# 1_INTERFACES_EXTERNAS.net
KiCad netlist of a schematic drawn in Altium Designer
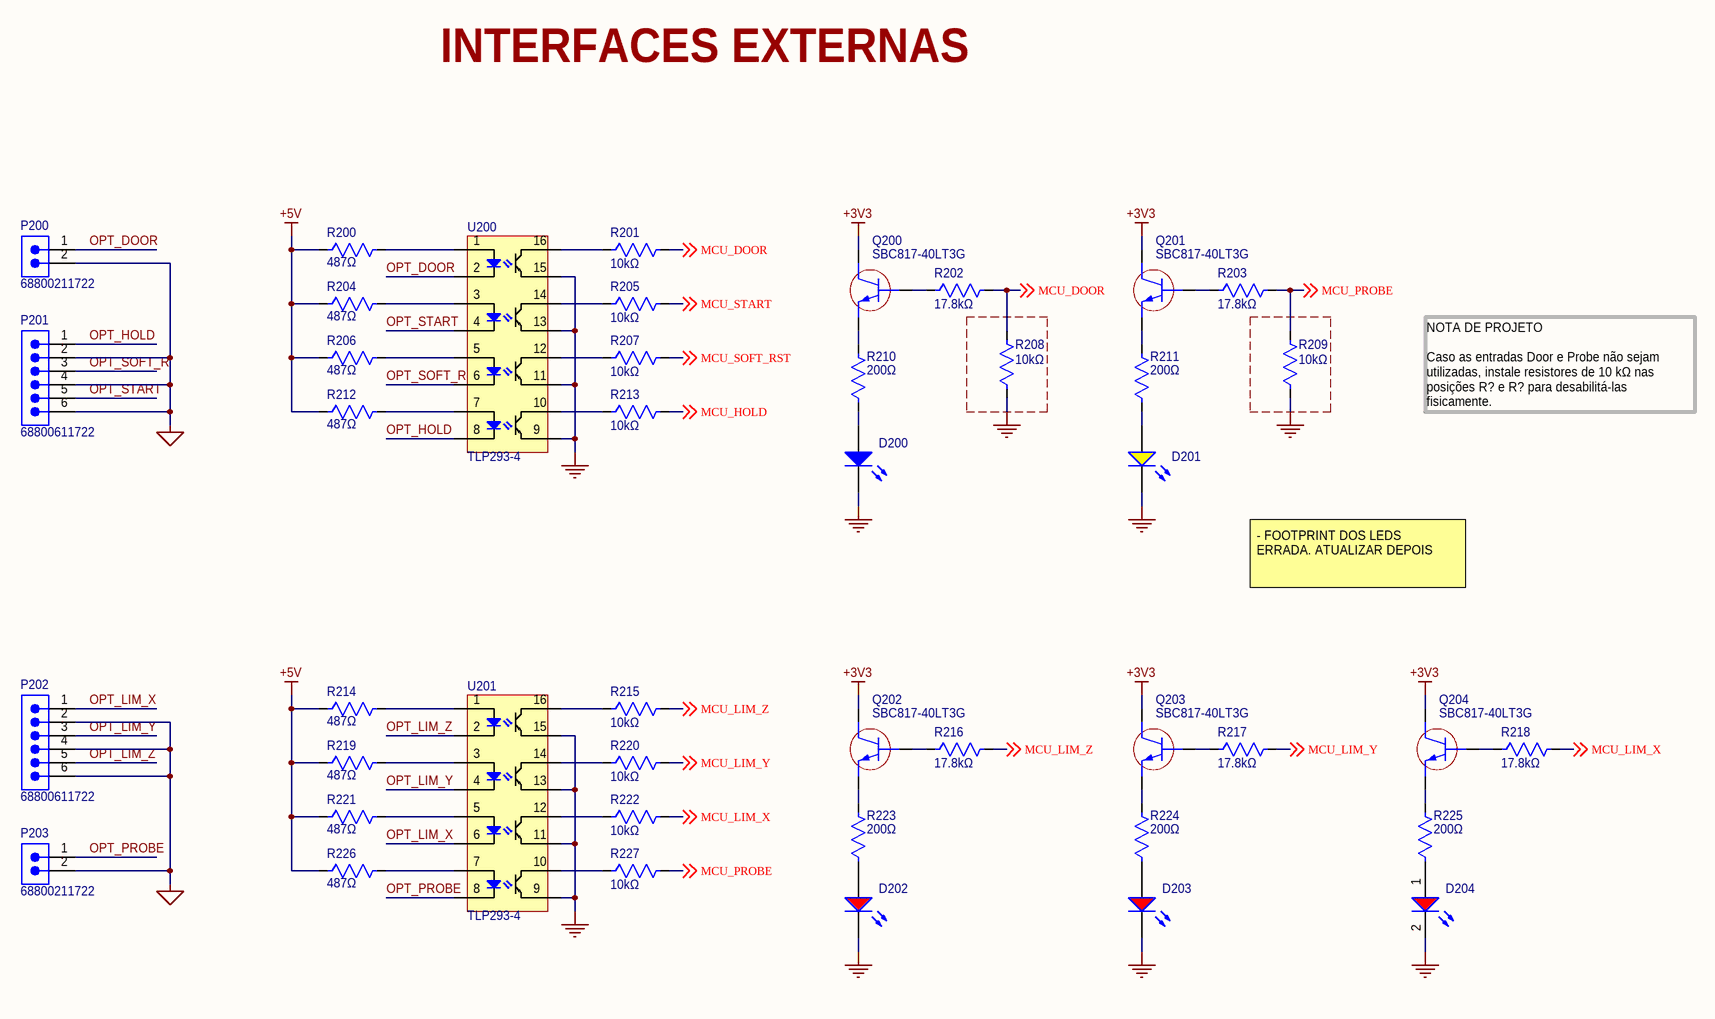
[diagram p0: 1_INTERFACES_EXTERNAS.SchDoc]

(export (version "E")
  (design (tool "Eeschema 10.0.6"))
  (components
    (comp (ref "D200")
      (value "Blue, 3.2V, 140deg")
      (footprint "WL-SMCW_0603_150060xx75003")
      (description "WL-SMCW Mono-color Chip LED Waterclear, SMT, size 0603, Blue, 3.2V, 140°")
      (fields
        (field (name "MANUFACTURER PART NUMBER") "150060BS75003")
        (field (name "MANUFACTURER") "Wurth Elektronik")
      )
      (libsource (lib "WE - Optoelectronic Components") (part "LED_Blue_1A-2K"))
    )
    (comp (ref "D201")
      (value "Yellow, 2V, 140deg")
      (footprint "WL-SMCW_0603_150060xx75000")
      (description "WL-SMCW Mono-color Chip LED Waterclear, SMT, size 0603, Yellow, 2V, 140°")
      (fields
        (field (name "MANUFACTURER PART NUMBER") "150060YS75000")
        (field (name "MANUFACTURER") "Wurth Elektronik")
      )
      (libsource (lib "WE - Optoelectronic Components") (part "LED_Yellow_2A-1K"))
    )
    (comp (ref "D202")
      (value "Red, 2V, 140deg")
      (footprint "WL-SMCW_0603_150060xx75003")
      (description "WL-SMCW Mono-color Chip LED Waterclear, SMT, size 0603, Red, 2V, 140°")
      (fields
        (field (name "MANUFACTURER PART NUMBER") "150060RS75003")
        (field (name "MANUFACTURER") "Wurth Elektronik")
      )
      (libsource (lib "") (part "LED_Red_1A-2K_1"))
    )
    (comp (ref "D203")
      (value "Red, 2V, 140deg")
      (footprint "WL-SMCW_0603_150060xx75003")
      (description "WL-SMCW Mono-color Chip LED Waterclear, SMT, size 0603, Red, 2V, 140°")
      (fields
        (field (name "MANUFACTURER PART NUMBER") "150060RS75003")
        (field (name "MANUFACTURER") "Wurth Elektronik")
      )
      (libsource (lib "") (part "LED_Red_1A-2K_1"))
    )
    (comp (ref "D204")
      (value "Red, 2V, 140deg")
      (footprint "WL-SMCW_0603_150060xx75003")
      (description "WL-SMCW Mono-color Chip LED Waterclear, SMT, size 0603, Red, 2V, 140°")
      (fields
        (field (name "MANUFACTURER PART NUMBER") "150060RS75003")
        (field (name "MANUFACTURER") "Wurth Elektronik")
      )
      (libsource (lib "WE - Optoelectronic Components") (part "LED_Red_1A-2K"))
    )
    (comp (ref "P200")
      (value "68800211722")
      (footprint "68800211722")
      (description "WR-WTB “J” Type THT Male Horizontal Shrouded Header, pitch 2.5 mm, 2 pins")
      (fields (field (name "MANUFACTURER") "Wurth Elektronik"))
      (libsource (lib "WE - Electromechanical Components") (part "Header_Male_1R_02P"))
    )
    (comp (ref "P201")
      (value "68800611722")
      (footprint "68800611722")
      (description "WR-WTB “J” Type THT Male Horizontal Shrouded Header, pitch 2.5 mm, 6 pins")
      (fields (field (name "MANUFACTURER") "Wurth Elektronik"))
      (libsource (lib "WE - Electromechanical Components") (part "Header_Male_1R_06P"))
    )
    (comp (ref "P202")
      (value "68800611722")
      (footprint "68800611722")
      (description "WR-WTB “J” Type THT Male Horizontal Shrouded Header, pitch 2.5 mm, 6 pins")
      (fields (field (name "MANUFACTURER") "Wurth Elektronik"))
      (libsource (lib "WE - Electromechanical Components") (part "Header_Male_1R_06P"))
    )
    (comp (ref "P203")
      (value "68800211722")
      (footprint "68800211722")
      (description "WR-WTB “J” Type THT Male Horizontal Shrouded Header, pitch 2.5 mm, 2 pins")
      (fields (field (name "MANUFACTURER") "Wurth Elektronik"))
      (libsource (lib "WE - Electromechanical Components") (part "Header_Male_1R_02P"))
    )
    (comp (ref "Q200")
      (value "SBC817-40LT3G")
      (footprint "SOT-23-3")
      (description "TRANS NPN 45V 0.5A SOT23-3")
      (fields (field (name "MANUFACTURER") "onsemi"))
      (libsource (lib "Transistors") (part "SBC817-40LT3G"))
    )
    (comp (ref "Q201")
      (value "SBC817-40LT3G")
      (footprint "SOT-23-3")
      (description "TRANS NPN 45V 0.5A SOT23-3")
      (fields (field (name "MANUFACTURER") "onsemi"))
      (libsource (lib "Transistors") (part "SBC817-40LT3G"))
    )
    (comp (ref "Q202")
      (value "SBC817-40LT3G")
      (footprint "SOT-23-3")
      (description "TRANS NPN 45V 0.5A SOT23-3")
      (fields (field (name "MANUFACTURER") "onsemi"))
      (libsource (lib "Transistors") (part "SBC817-40LT3G"))
    )
    (comp (ref "Q203")
      (value "SBC817-40LT3G")
      (footprint "SOT-23-3")
      (description "TRANS NPN 45V 0.5A SOT23-3")
      (fields (field (name "MANUFACTURER") "onsemi"))
      (libsource (lib "Transistors") (part "SBC817-40LT3G"))
    )
    (comp (ref "Q204")
      (value "SBC817-40LT3G")
      (footprint "SOT-23-3")
      (description "TRANS NPN 45V 0.5A SOT23-3")
      (fields (field (name "MANUFACTURER") "onsemi"))
      (libsource (lib "Transistors") (part "SBC817-40LT3G"))
    )
    (comp (ref "R200")
      (value "487Ω")
      (footprint "0603-WAVE")
      (description "RES 487 OHM 1% 1/10W 0603")
      (fields
        (field (name "MANUFACTURER PART NUMBER") "RC0603FR-07487RL")
        (field (name "MANUFACTURER") "Yageo Group")
      )
      (libsource (lib "Resistors-0603-E96-Yageo") (part "RC0603FR-07487RL"))
    )
    (comp (ref "R201")
      (value "10kΩ")
      (footprint "0603-WAVE")
      (description "RES 10K OHM 1% 1/10W 0603")
      (fields
        (field (name "MANUFACTURER PART NUMBER") "RC0603FR-0710KL")
        (field (name "MANUFACTURER") "Yageo Group")
      )
      (libsource (lib "Resistors-0603-E96-Yageo") (part "RC0603FR-0710KL"))
    )
    (comp (ref "R202")
      (value "17.8kΩ")
      (footprint "0603-WAVE")
      (description "RES 17.8K OHM 1% 1/10W 0603")
      (fields
        (field (name "MANUFACTURER PART NUMBER") "RC0603FR-0717K8L")
        (field (name "MANUFACTURER") "Yageo Group")
      )
      (libsource (lib "Resistors-0603-E96-Yageo") (part "RC0603FR-0717K8L"))
    )
    (comp (ref "R203")
      (value "17.8kΩ")
      (footprint "0603-WAVE")
      (description "RES 17.8K OHM 1% 1/10W 0603")
      (fields
        (field (name "MANUFACTURER PART NUMBER") "RC0603FR-0717K8L")
        (field (name "MANUFACTURER") "Yageo Group")
      )
      (libsource (lib "Resistors-0603-E96-Yageo") (part "RC0603FR-0717K8L"))
    )
    (comp (ref "R204")
      (value "487Ω")
      (footprint "0603-WAVE")
      (description "RES 487 OHM 1% 1/10W 0603")
      (fields
        (field (name "MANUFACTURER PART NUMBER") "RC0603FR-07487RL")
        (field (name "MANUFACTURER") "Yageo Group")
      )
      (libsource (lib "Resistors-0603-E96-Yageo") (part "RC0603FR-07487RL"))
    )
    (comp (ref "R205")
      (value "10kΩ")
      (footprint "0603-WAVE")
      (description "RES 10K OHM 1% 1/10W 0603")
      (fields
        (field (name "MANUFACTURER PART NUMBER") "RC0603FR-0710KL")
        (field (name "MANUFACTURER") "Yageo Group")
      )
      (libsource (lib "Resistors-0603-E96-Yageo") (part "RC0603FR-0710KL"))
    )
    (comp (ref "R206")
      (value "487Ω")
      (footprint "0603-WAVE")
      (description "RES 487 OHM 1% 1/10W 0603")
      (fields
        (field (name "MANUFACTURER PART NUMBER") "RC0603FR-07487RL")
        (field (name "MANUFACTURER") "Yageo Group")
      )
      (libsource (lib "Resistors-0603-E96-Yageo") (part "RC0603FR-07487RL"))
    )
    (comp (ref "R207")
      (value "10kΩ")
      (footprint "0603-WAVE")
      (description "RES 10K OHM 1% 1/10W 0603")
      (fields
        (field (name "MANUFACTURER PART NUMBER") "RC0603FR-0710KL")
        (field (name "MANUFACTURER") "Yageo Group")
      )
      (libsource (lib "Resistors-0603-E96-Yageo") (part "RC0603FR-0710KL"))
    )
    (comp (ref "R208")
      (value "10kΩ")
      (footprint "0603-WAVE")
      (description "RES 10K OHM 1% 1/10W 0603")
      (fields
        (field (name "MANUFACTURER PART NUMBER") "RC0603FR-0710KL")
        (field (name "MANUFACTURER") "Yageo Group")
      )
      (libsource (lib "Resistors-0603-E96-Yageo") (part "RC0603FR-0710KL"))
    )
    (comp (ref "R209")
      (value "10kΩ")
      (footprint "0603-WAVE")
      (description "RES 10K OHM 1% 1/10W 0603")
      (fields
        (field (name "MANUFACTURER PART NUMBER") "RC0603FR-0710KL")
        (field (name "MANUFACTURER") "Yageo Group")
      )
      (libsource (lib "Resistors-0603-E96-Yageo") (part "RC0603FR-0710KL"))
    )
    (comp (ref "R210")
      (value "200Ω")
      (footprint "0603-WAVE")
      (description "RES 200 OHM 1% 1/10W 0603")
      (fields
        (field (name "MANUFACTURER PART NUMBER") "RC0603FR-07200RL")
        (field (name "MANUFACTURER") "Yageo Group")
      )
      (libsource (lib "Resistors-0603-E96-Yageo") (part "RC0603FR-07200RL"))
    )
    (comp (ref "R211")
      (value "200Ω")
      (footprint "0603-WAVE")
      (description "RES 200 OHM 1% 1/10W 0603")
      (fields
        (field (name "MANUFACTURER PART NUMBER") "RC0603FR-07200RL")
        (field (name "MANUFACTURER") "Yageo Group")
      )
      (libsource (lib "Resistors-0603-E96-Yageo") (part "RC0603FR-07200RL"))
    )
    (comp (ref "R212")
      (value "487Ω")
      (footprint "0603-WAVE")
      (description "RES 487 OHM 1% 1/10W 0603")
      (fields
        (field (name "MANUFACTURER PART NUMBER") "RC0603FR-07487RL")
        (field (name "MANUFACTURER") "Yageo Group")
      )
      (libsource (lib "Resistors-0603-E96-Yageo") (part "RC0603FR-07487RL"))
    )
    (comp (ref "R213")
      (value "10kΩ")
      (footprint "0603-WAVE")
      (description "RES 10K OHM 1% 1/10W 0603")
      (fields
        (field (name "MANUFACTURER PART NUMBER") "RC0603FR-0710KL")
        (field (name "MANUFACTURER") "Yageo Group")
      )
      (libsource (lib "Resistors-0603-E96-Yageo") (part "RC0603FR-0710KL"))
    )
    (comp (ref "R214")
      (value "487Ω")
      (footprint "0603-WAVE")
      (description "RES 487 OHM 1% 1/10W 0603")
      (fields
        (field (name "MANUFACTURER PART NUMBER") "RC0603FR-07487RL")
        (field (name "MANUFACTURER") "Yageo Group")
      )
      (libsource (lib "Resistors-0603-E96-Yageo") (part "RC0603FR-07487RL"))
    )
    (comp (ref "R215")
      (value "10kΩ")
      (footprint "0603-WAVE")
      (description "RES 10K OHM 1% 1/10W 0603")
      (fields
        (field (name "MANUFACTURER PART NUMBER") "RC0603FR-0710KL")
        (field (name "MANUFACTURER") "Yageo Group")
      )
      (libsource (lib "Resistors-0603-E96-Yageo") (part "RC0603FR-0710KL"))
    )
    (comp (ref "R216")
      (value "17.8kΩ")
      (footprint "0603-WAVE")
      (description "RES 17.8K OHM 1% 1/10W 0603")
      (fields
        (field (name "MANUFACTURER PART NUMBER") "RC0603FR-0717K8L")
        (field (name "MANUFACTURER") "Yageo Group")
      )
      (libsource (lib "Resistors-0603-E96-Yageo") (part "RC0603FR-0717K8L"))
    )
    (comp (ref "R217")
      (value "17.8kΩ")
      (footprint "0603-WAVE")
      (description "RES 17.8K OHM 1% 1/10W 0603")
      (fields
        (field (name "MANUFACTURER PART NUMBER") "RC0603FR-0717K8L")
        (field (name "MANUFACTURER") "Yageo Group")
      )
      (libsource (lib "Resistors-0603-E96-Yageo") (part "RC0603FR-0717K8L"))
    )
    (comp (ref "R218")
      (value "17.8kΩ")
      (footprint "0603-WAVE")
      (description "RES 17.8K OHM 1% 1/10W 0603")
      (fields
        (field (name "MANUFACTURER PART NUMBER") "RC0603FR-0717K8L")
        (field (name "MANUFACTURER") "Yageo Group")
      )
      (libsource (lib "Resistors-0603-E96-Yageo") (part "RC0603FR-0717K8L"))
    )
    (comp (ref "R219")
      (value "487Ω")
      (footprint "0603-WAVE")
      (description "RES 487 OHM 1% 1/10W 0603")
      (fields
        (field (name "MANUFACTURER PART NUMBER") "RC0603FR-07487RL")
        (field (name "MANUFACTURER") "Yageo Group")
      )
      (libsource (lib "Resistors-0603-E96-Yageo") (part "RC0603FR-07487RL"))
    )
    (comp (ref "R220")
      (value "10kΩ")
      (footprint "0603-WAVE")
      (description "RES 10K OHM 1% 1/10W 0603")
      (fields
        (field (name "MANUFACTURER PART NUMBER") "RC0603FR-0710KL")
        (field (name "MANUFACTURER") "Yageo Group")
      )
      (libsource (lib "Resistors-0603-E96-Yageo") (part "RC0603FR-0710KL"))
    )
    (comp (ref "R221")
      (value "487Ω")
      (footprint "0603-WAVE")
      (description "RES 487 OHM 1% 1/10W 0603")
      (fields
        (field (name "MANUFACTURER PART NUMBER") "RC0603FR-07487RL")
        (field (name "MANUFACTURER") "Yageo Group")
      )
      (libsource (lib "Resistors-0603-E96-Yageo") (part "RC0603FR-07487RL"))
    )
    (comp (ref "R222")
      (value "10kΩ")
      (footprint "0603-WAVE")
      (description "RES 10K OHM 1% 1/10W 0603")
      (fields
        (field (name "MANUFACTURER PART NUMBER") "RC0603FR-0710KL")
        (field (name "MANUFACTURER") "Yageo Group")
      )
      (libsource (lib "Resistors-0603-E96-Yageo") (part "RC0603FR-0710KL"))
    )
    (comp (ref "R223")
      (value "200Ω")
      (footprint "0603-WAVE")
      (description "RES 200 OHM 1% 1/10W 0603")
      (fields
        (field (name "MANUFACTURER PART NUMBER") "RC0603FR-07200RL")
        (field (name "MANUFACTURER") "Yageo Group")
      )
      (libsource (lib "Resistors-0603-E96-Yageo") (part "RC0603FR-07200RL"))
    )
    (comp (ref "R224")
      (value "200Ω")
      (footprint "0603-WAVE")
      (description "RES 200 OHM 1% 1/10W 0603")
      (fields
        (field (name "MANUFACTURER PART NUMBER") "RC0603FR-07200RL")
        (field (name "MANUFACTURER") "Yageo Group")
      )
      (libsource (lib "Resistors-0603-E96-Yageo") (part "RC0603FR-07200RL"))
    )
    (comp (ref "R225")
      (value "200Ω")
      (footprint "0603-WAVE")
      (description "RES 200 OHM 1% 1/10W 0603")
      (fields
        (field (name "MANUFACTURER PART NUMBER") "RC0603FR-07200RL")
        (field (name "MANUFACTURER") "Yageo Group")
      )
      (libsource (lib "Resistors-0603-E96-Yageo") (part "RC0603FR-07200RL"))
    )
    (comp (ref "R226")
      (value "487Ω")
      (footprint "0603-WAVE")
      (description "RES 487 OHM 1% 1/10W 0603")
      (fields
        (field (name "MANUFACTURER PART NUMBER") "RC0603FR-07487RL")
        (field (name "MANUFACTURER") "Yageo Group")
      )
      (libsource (lib "Resistors-0603-E96-Yageo") (part "RC0603FR-07487RL"))
    )
    (comp (ref "R227")
      (value "10kΩ")
      (footprint "0603-WAVE")
      (description "RES 10K OHM 1% 1/10W 0603")
      (fields
        (field (name "MANUFACTURER PART NUMBER") "RC0603FR-0710KL")
        (field (name "MANUFACTURER") "Yageo Group")
      )
      (libsource (lib "Resistors-0603-E96-Yageo") (part "RC0603FR-0710KL"))
    )
    (comp (ref "U200")
      (value "TLP293-4")
      (footprint "SO-16")
      (description "OPTOISO 3.75KV 4CH TRANS 16-SO")
      (fields
        (field (name "MANUFACTURER") "Toshiba")
        (field (name "MANUFACTURER PART NUMBER") "TLP293-4(TP,E")
      )
      (libsource (lib "Optocouplers") (part "TLP293-4"))
    )
    (comp (ref "U201")
      (value "TLP293-4")
      (footprint "SO-16")
      (description "OPTOISO 3.75KV 4CH TRANS 16-SO")
      (fields
        (field (name "MANUFACTURER") "Toshiba")
        (field (name "MANUFACTURER PART NUMBER") "TLP293-4(TP,E")
      )
      (libsource (lib "Optocouplers") (part "TLP293-4"))
    )
  )
  (nets
    (net (code "1") (name "+3V3") (class "Default")
      (node (ref "Q200") (pin "3") (pinfunction "C_3") (pintype "passive"))
      (node (ref "Q201") (pin "3") (pinfunction "C_3") (pintype "passive"))
      (node (ref "Q202") (pin "3") (pinfunction "C_3") (pintype "passive"))
      (node (ref "Q203") (pin "3") (pinfunction "C_3") (pintype "passive"))
      (node (ref "Q204") (pin "3") (pinfunction "C_3") (pintype "passive"))
    )
    (net (code "2") (name "+5V") (class "Default")
      (node (ref "R200") (pin "1") (pinfunction "1_1") (pintype "passive"))
      (node (ref "R204") (pin "1") (pinfunction "1_1") (pintype "passive"))
      (node (ref "R206") (pin "1") (pinfunction "1_1") (pintype "passive"))
      (node (ref "R212") (pin "1") (pinfunction "1_1") (pintype "passive"))
      (node (ref "R214") (pin "1") (pinfunction "1_1") (pintype "passive"))
      (node (ref "R219") (pin "1") (pinfunction "1_1") (pintype "passive"))
      (node (ref "R221") (pin "1") (pinfunction "1_1") (pintype "passive"))
      (node (ref "R226") (pin "1") (pinfunction "1_1") (pintype "passive"))
    )
    (net (code "3") (name "/OPT_DOOR") (class "Default")
      (node (ref "P200") (pin "1") (pinfunction "1_1") (pintype "passive"))
      (node (ref "U200") (pin "2") (pinfunction "2_2") (pintype "passive"))
    )
    (net (code "4") (name "/OPT_HOLD") (class "Default")
      (node (ref "P201") (pin "1") (pinfunction "1_1") (pintype "passive"))
      (node (ref "U200") (pin "8") (pinfunction "8_8") (pintype "passive"))
    )
    (net (code "5") (name "/OPT_LIM_X") (class "Default")
      (node (ref "P202") (pin "1") (pinfunction "1_1") (pintype "passive"))
      (node (ref "U201") (pin "6") (pinfunction "6_6") (pintype "passive"))
    )
    (net (code "6") (name "/OPT_LIM_Y") (class "Default")
      (node (ref "P202") (pin "3") (pinfunction "3_3") (pintype "passive"))
      (node (ref "U201") (pin "4") (pinfunction "4_4") (pintype "passive"))
    )
    (net (code "7") (name "/OPT_LIM_Z") (class "Default")
      (node (ref "P202") (pin "5") (pinfunction "5_5") (pintype "passive"))
      (node (ref "U201") (pin "2") (pinfunction "2_2") (pintype "passive"))
    )
    (net (code "8") (name "/OPT_PROBE") (class "Default")
      (node (ref "P203") (pin "1") (pinfunction "1_1") (pintype "passive"))
      (node (ref "U201") (pin "8") (pinfunction "8_8") (pintype "passive"))
    )
    (net (code "9") (name "/OPT_SOFT_R") (class "Default")
      (node (ref "P201") (pin "3") (pinfunction "3_3") (pintype "passive"))
      (node (ref "U200") (pin "6") (pinfunction "6_6") (pintype "passive"))
    )
    (net (code "10") (name "/OPT_START") (class "Default")
      (node (ref "P201") (pin "5") (pinfunction "5_5") (pintype "passive"))
      (node (ref "U200") (pin "4") (pinfunction "4_4") (pintype "passive"))
    )
    (net (code "11") (name "GND") (class "Default")
      (node (ref "D200") (pin "2") (pinfunction "K_2") (pintype "passive"))
      (node (ref "D201") (pin "1") (pinfunction "K_1") (pintype "passive"))
      (node (ref "D202") (pin "2") (pinfunction "K_2") (pintype "passive"))
      (node (ref "D203") (pin "2") (pinfunction "K_2") (pintype "passive"))
      (node (ref "D204") (pin "2") (pinfunction "K_2") (pintype "passive"))
      (node (ref "R208") (pin "1") (pinfunction "1_1") (pintype "passive"))
      (node (ref "R209") (pin "1") (pinfunction "1_1") (pintype "passive"))
      (node (ref "U200") (pin "11") (pinfunction "11_11") (pintype "passive"))
      (node (ref "U200") (pin "13") (pinfunction "13_13") (pintype "passive"))
      (node (ref "U200") (pin "15") (pinfunction "15_15") (pintype "passive"))
      (node (ref "U200") (pin "9") (pinfunction "9_9") (pintype "passive"))
      (node (ref "U201") (pin "11") (pinfunction "11_11") (pintype "passive"))
      (node (ref "U201") (pin "13") (pinfunction "13_13") (pintype "passive"))
      (node (ref "U201") (pin "15") (pinfunction "15_15") (pintype "passive"))
      (node (ref "U201") (pin "9") (pinfunction "9_9") (pintype "passive"))
    )
    (net (code "12") (name "GND_ISO") (class "Default")
      (node (ref "P200") (pin "2") (pinfunction "2_2") (pintype "passive"))
      (node (ref "P201") (pin "2") (pinfunction "2_2") (pintype "passive"))
      (node (ref "P201") (pin "4") (pinfunction "4_4") (pintype "passive"))
      (node (ref "P201") (pin "6") (pinfunction "6_6") (pintype "passive"))
      (node (ref "P202") (pin "2") (pinfunction "2_2") (pintype "passive"))
      (node (ref "P202") (pin "4") (pinfunction "4_4") (pintype "passive"))
      (node (ref "P202") (pin "6") (pinfunction "6_6") (pintype "passive"))
      (node (ref "P203") (pin "2") (pinfunction "2_2") (pintype "passive"))
    )
    (net (code "13") (name "MCU_DOOR") (class "Default")
      (node (ref "R201") (pin "2") (pinfunction "2_2") (pintype "passive"))
      (node (ref "R202") (pin "2") (pinfunction "2_2") (pintype "passive"))
      (node (ref "R208") (pin "2") (pinfunction "2_2") (pintype "passive"))
    )
    (net (code "14") (name "MCU_HOLD") (class "Default")
      (node (ref "R213") (pin "2") (pinfunction "2_2") (pintype "passive"))
    )
    (net (code "15") (name "MCU_LIM_X") (class "Default")
      (node (ref "R218") (pin "2") (pinfunction "2_2") (pintype "passive"))
      (node (ref "R222") (pin "2") (pinfunction "2_2") (pintype "passive"))
    )
    (net (code "16") (name "MCU_LIM_Y") (class "Default")
      (node (ref "R217") (pin "2") (pinfunction "2_2") (pintype "passive"))
      (node (ref "R220") (pin "2") (pinfunction "2_2") (pintype "passive"))
    )
    (net (code "17") (name "MCU_LIM_Z") (class "Default")
      (node (ref "R215") (pin "2") (pinfunction "2_2") (pintype "passive"))
      (node (ref "R216") (pin "2") (pinfunction "2_2") (pintype "passive"))
    )
    (net (code "18") (name "MCU_PROBE") (class "Default")
      (node (ref "R203") (pin "2") (pinfunction "2_2") (pintype "passive"))
      (node (ref "R209") (pin "2") (pinfunction "2_2") (pintype "passive"))
      (node (ref "R227") (pin "2") (pinfunction "2_2") (pintype "passive"))
    )
    (net (code "19") (name "MCU_SOFT_RST") (class "Default")
      (node (ref "R207") (pin "2") (pinfunction "2_2") (pintype "passive"))
    )
    (net (code "20") (name "MCU_START") (class "Default")
      (node (ref "R205") (pin "2") (pinfunction "2_2") (pintype "passive"))
    )
    (net (code "21") (name "Net-(D200-A)") (class "Default")
      (node (ref "D200") (pin "1") (pinfunction "A_1") (pintype "passive"))
      (node (ref "R210") (pin "1") (pinfunction "1_1") (pintype "passive"))
    )
    (net (code "22") (name "Net-(D201-A)") (class "Default")
      (node (ref "D201") (pin "2") (pinfunction "A_2") (pintype "passive"))
      (node (ref "R211") (pin "1") (pinfunction "1_1") (pintype "passive"))
    )
    (net (code "23") (name "Net-(D202-A)") (class "Default")
      (node (ref "D202") (pin "1") (pinfunction "A_1") (pintype "passive"))
      (node (ref "R223") (pin "1") (pinfunction "1_1") (pintype "passive"))
    )
    (net (code "24") (name "Net-(D203-A)") (class "Default")
      (node (ref "D203") (pin "1") (pinfunction "A_1") (pintype "passive"))
      (node (ref "R224") (pin "1") (pinfunction "1_1") (pintype "passive"))
    )
    (net (code "25") (name "Net-(D204-A)") (class "Default")
      (node (ref "D204") (pin "1") (pinfunction "A_1") (pintype "passive"))
      (node (ref "R225") (pin "1") (pinfunction "1_1") (pintype "passive"))
    )
    (net (code "26") (name "Net-(Q200-B)") (class "Default")
      (node (ref "Q200") (pin "1") (pinfunction "B_1") (pintype "passive"))
      (node (ref "R202") (pin "1") (pinfunction "1_1") (pintype "passive"))
    )
    (net (code "27") (name "Net-(Q200-E)") (class "Default")
      (node (ref "Q200") (pin "2") (pinfunction "E_2") (pintype "passive"))
      (node (ref "R210") (pin "2") (pinfunction "2_2") (pintype "passive"))
    )
    (net (code "28") (name "Net-(Q201-B)") (class "Default")
      (node (ref "Q201") (pin "1") (pinfunction "B_1") (pintype "passive"))
      (node (ref "R203") (pin "1") (pinfunction "1_1") (pintype "passive"))
    )
    (net (code "29") (name "Net-(Q201-E)") (class "Default")
      (node (ref "Q201") (pin "2") (pinfunction "E_2") (pintype "passive"))
      (node (ref "R211") (pin "2") (pinfunction "2_2") (pintype "passive"))
    )
    (net (code "30") (name "Net-(Q202-B)") (class "Default")
      (node (ref "Q202") (pin "1") (pinfunction "B_1") (pintype "passive"))
      (node (ref "R216") (pin "1") (pinfunction "1_1") (pintype "passive"))
    )
    (net (code "31") (name "Net-(Q202-E)") (class "Default")
      (node (ref "Q202") (pin "2") (pinfunction "E_2") (pintype "passive"))
      (node (ref "R223") (pin "2") (pinfunction "2_2") (pintype "passive"))
    )
    (net (code "32") (name "Net-(Q203-B)") (class "Default")
      (node (ref "Q203") (pin "1") (pinfunction "B_1") (pintype "passive"))
      (node (ref "R217") (pin "1") (pinfunction "1_1") (pintype "passive"))
    )
    (net (code "33") (name "Net-(Q203-E)") (class "Default")
      (node (ref "Q203") (pin "2") (pinfunction "E_2") (pintype "passive"))
      (node (ref "R224") (pin "2") (pinfunction "2_2") (pintype "passive"))
    )
    (net (code "34") (name "Net-(Q204-B)") (class "Default")
      (node (ref "Q204") (pin "1") (pinfunction "B_1") (pintype "passive"))
      (node (ref "R218") (pin "1") (pinfunction "1_1") (pintype "passive"))
    )
    (net (code "35") (name "Net-(Q204-E)") (class "Default")
      (node (ref "Q204") (pin "2") (pinfunction "E_2") (pintype "passive"))
      (node (ref "R225") (pin "2") (pinfunction "2_2") (pintype "passive"))
    )
    (net (code "36") (name "Net-(R200-Pad2)") (class "Default")
      (node (ref "R200") (pin "2") (pinfunction "2_2") (pintype "passive"))
      (node (ref "U200") (pin "1") (pinfunction "1_1") (pintype "passive"))
    )
    (net (code "37") (name "Net-(R201-Pad1)") (class "Default")
      (node (ref "R201") (pin "1") (pinfunction "1_1") (pintype "passive"))
      (node (ref "U200") (pin "16") (pinfunction "16_16") (pintype "passive"))
    )
    (net (code "38") (name "Net-(R204-Pad2)") (class "Default")
      (node (ref "R204") (pin "2") (pinfunction "2_2") (pintype "passive"))
      (node (ref "U200") (pin "3") (pinfunction "3_3") (pintype "passive"))
    )
    (net (code "39") (name "Net-(R205-Pad1)") (class "Default")
      (node (ref "R205") (pin "1") (pinfunction "1_1") (pintype "passive"))
      (node (ref "U200") (pin "14") (pinfunction "14_14") (pintype "passive"))
    )
    (net (code "40") (name "Net-(R206-Pad2)") (class "Default")
      (node (ref "R206") (pin "2") (pinfunction "2_2") (pintype "passive"))
      (node (ref "U200") (pin "5") (pinfunction "5_5") (pintype "passive"))
    )
    (net (code "41") (name "Net-(R207-Pad1)") (class "Default")
      (node (ref "R207") (pin "1") (pinfunction "1_1") (pintype "passive"))
      (node (ref "U200") (pin "12") (pinfunction "12_12") (pintype "passive"))
    )
    (net (code "42") (name "Net-(R212-Pad2)") (class "Default")
      (node (ref "R212") (pin "2") (pinfunction "2_2") (pintype "passive"))
      (node (ref "U200") (pin "7") (pinfunction "7_7") (pintype "passive"))
    )
    (net (code "43") (name "Net-(R213-Pad1)") (class "Default")
      (node (ref "R213") (pin "1") (pinfunction "1_1") (pintype "passive"))
      (node (ref "U200") (pin "10") (pinfunction "10_10") (pintype "passive"))
    )
    (net (code "44") (name "Net-(R214-Pad2)") (class "Default")
      (node (ref "R214") (pin "2") (pinfunction "2_2") (pintype "passive"))
      (node (ref "U201") (pin "1") (pinfunction "1_1") (pintype "passive"))
    )
    (net (code "45") (name "Net-(R215-Pad1)") (class "Default")
      (node (ref "R215") (pin "1") (pinfunction "1_1") (pintype "passive"))
      (node (ref "U201") (pin "16") (pinfunction "16_16") (pintype "passive"))
    )
    (net (code "46") (name "Net-(R219-Pad2)") (class "Default")
      (node (ref "R219") (pin "2") (pinfunction "2_2") (pintype "passive"))
      (node (ref "U201") (pin "3") (pinfunction "3_3") (pintype "passive"))
    )
    (net (code "47") (name "Net-(R220-Pad1)") (class "Default")
      (node (ref "R220") (pin "1") (pinfunction "1_1") (pintype "passive"))
      (node (ref "U201") (pin "14") (pinfunction "14_14") (pintype "passive"))
    )
    (net (code "48") (name "Net-(R221-Pad2)") (class "Default")
      (node (ref "R221") (pin "2") (pinfunction "2_2") (pintype "passive"))
      (node (ref "U201") (pin "5") (pinfunction "5_5") (pintype "passive"))
    )
    (net (code "49") (name "Net-(R222-Pad1)") (class "Default")
      (node (ref "R222") (pin "1") (pinfunction "1_1") (pintype "passive"))
      (node (ref "U201") (pin "12") (pinfunction "12_12") (pintype "passive"))
    )
    (net (code "50") (name "Net-(R226-Pad2)") (class "Default")
      (node (ref "R226") (pin "2") (pinfunction "2_2") (pintype "passive"))
      (node (ref "U201") (pin "7") (pinfunction "7_7") (pintype "passive"))
    )
    (net (code "51") (name "Net-(R227-Pad1)") (class "Default")
      (node (ref "R227") (pin "1") (pinfunction "1_1") (pintype "passive"))
      (node (ref "U201") (pin "10") (pinfunction "10_10") (pintype "passive"))
    )
  )
)
